# tommyprom.net
KiCad netlist of a schematic drawn in EAGLE
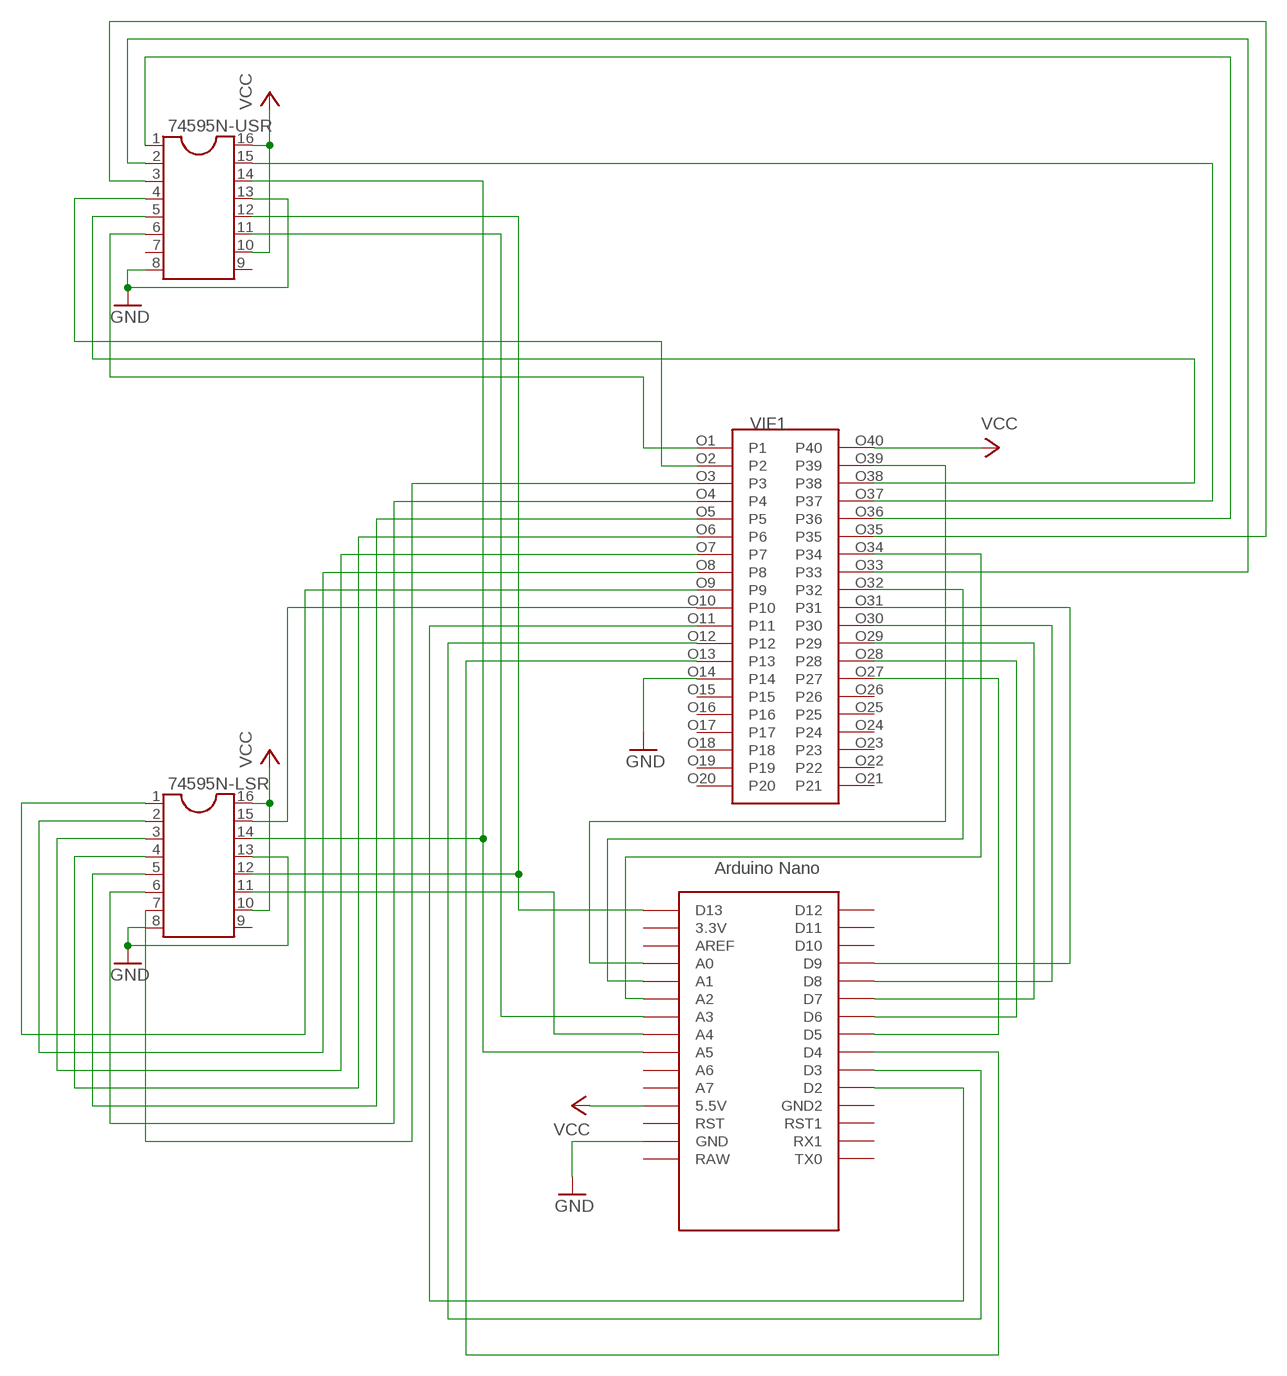
[diagram p0: schematic, sheet 1]

(export (version "E")
  (design (tool "Eeschema 10.0.6"))
  (components
    (comp (ref "74595N-LSR")
      (value "DIL16S")
      (footprint "eagle-import:SOCKET-16")
      (libsource (lib "eagle-import") (part "DIL16S"))
    )
    (comp (ref "74595N-USR")
      (value "DIL16S")
      (footprint "eagle-import:SOCKET-16")
      (libsource (lib "eagle-import") (part "DIL16S"))
    )
    (comp (ref "U$1")
      (value "NANO")
      (footprint "eagle-import:NANO")
      (libsource (lib "eagle-import") (part "NANO"))
    )
    (comp (ref "VIF1")
      (value "40-6554-10DIP")
      (footprint "eagle-import:40-6554-10")
      (libsource (lib "eagle-import") (part "40-6554-10DIP"))
    )
  )
  (nets
    (net (code "1") (name "GND") (class "Default")
      (node (ref "74595N-LSR") (pin "13") (pinfunction "13_13") (pintype "passive"))
      (node (ref "74595N-LSR") (pin "8") (pinfunction "8_8") (pintype "passive"))
      (node (ref "74595N-USR") (pin "13") (pinfunction "13_13") (pintype "passive"))
      (node (ref "74595N-USR") (pin "8") (pinfunction "8_8") (pintype "passive"))
      (node (ref "U$1") (pin "GND") (pinfunction "GND_GND") (pintype "bidirectional"))
      (node (ref "VIF1") (pin "O14") (pinfunction "P14_O14") (pintype "bidirectional"))
    )
    (net (code "2") (name "Net-(74595N-LSR-Pad11)") (class "Default")
      (node (ref "74595N-LSR") (pin "11") (pinfunction "11_11") (pintype "passive"))
      (node (ref "U$1") (pin "A4") (pinfunction "A4_A4") (pintype "bidirectional"))
    )
    (net (code "3") (name "Net-(74595N-LSR-Pad12)") (class "Default")
      (node (ref "74595N-LSR") (pin "12") (pinfunction "12_12") (pintype "passive"))
      (node (ref "74595N-USR") (pin "12") (pinfunction "12_12") (pintype "passive"))
      (node (ref "U$1") (pin "D13") (pinfunction "D13_D13") (pintype "bidirectional"))
    )
    (net (code "4") (name "Net-(74595N-LSR-Pad14)") (class "Default")
      (node (ref "74595N-LSR") (pin "14") (pinfunction "14_14") (pintype "passive"))
      (node (ref "74595N-USR") (pin "14") (pinfunction "14_14") (pintype "passive"))
      (node (ref "U$1") (pin "A5") (pinfunction "A5_A5") (pintype "bidirectional"))
    )
    (net (code "5") (name "Net-(74595N-USR-Pad11)") (class "Default")
      (node (ref "74595N-USR") (pin "11") (pinfunction "11_11") (pintype "passive"))
      (node (ref "U$1") (pin "A3") (pinfunction "A3_A3") (pintype "bidirectional"))
    )
    (net (code "6") (name "Net-(VIF1-P1)") (class "Default")
      (node (ref "74595N-USR") (pin "6") (pinfunction "6_6") (pintype "passive"))
      (node (ref "VIF1") (pin "O1") (pinfunction "P1_O1") (pintype "bidirectional"))
    )
    (net (code "7") (name "Net-(VIF1-P2)") (class "Default")
      (node (ref "74595N-USR") (pin "4") (pinfunction "4_4") (pintype "passive"))
      (node (ref "VIF1") (pin "O2") (pinfunction "P2_O2") (pintype "bidirectional"))
    )
    (net (code "8") (name "Net-(VIF1-P3)") (class "Default")
      (node (ref "74595N-LSR") (pin "7") (pinfunction "7_7") (pintype "passive"))
      (node (ref "VIF1") (pin "O3") (pinfunction "P3_O3") (pintype "bidirectional"))
    )
    (net (code "9") (name "Net-(VIF1-P4)") (class "Default")
      (node (ref "74595N-LSR") (pin "6") (pinfunction "6_6") (pintype "passive"))
      (node (ref "VIF1") (pin "O4") (pinfunction "P4_O4") (pintype "bidirectional"))
    )
    (net (code "10") (name "Net-(VIF1-P5)") (class "Default")
      (node (ref "74595N-LSR") (pin "5") (pinfunction "5_5") (pintype "passive"))
      (node (ref "VIF1") (pin "O5") (pinfunction "P5_O5") (pintype "bidirectional"))
    )
    (net (code "11") (name "Net-(VIF1-P6)") (class "Default")
      (node (ref "74595N-LSR") (pin "4") (pinfunction "4_4") (pintype "passive"))
      (node (ref "VIF1") (pin "O6") (pinfunction "P6_O6") (pintype "bidirectional"))
    )
    (net (code "12") (name "Net-(VIF1-P7)") (class "Default")
      (node (ref "74595N-LSR") (pin "3") (pinfunction "3_3") (pintype "passive"))
      (node (ref "VIF1") (pin "O7") (pinfunction "P7_O7") (pintype "bidirectional"))
    )
    (net (code "13") (name "Net-(VIF1-P8)") (class "Default")
      (node (ref "74595N-LSR") (pin "2") (pinfunction "2_2") (pintype "passive"))
      (node (ref "VIF1") (pin "O8") (pinfunction "P8_O8") (pintype "bidirectional"))
    )
    (net (code "14") (name "Net-(VIF1-P9)") (class "Default")
      (node (ref "74595N-LSR") (pin "1") (pinfunction "1_1") (pintype "passive"))
      (node (ref "VIF1") (pin "O9") (pinfunction "P9_O9") (pintype "bidirectional"))
    )
    (net (code "15") (name "Net-(VIF1-P10)") (class "Default")
      (node (ref "74595N-LSR") (pin "15") (pinfunction "15_15") (pintype "passive"))
      (node (ref "VIF1") (pin "O10") (pinfunction "P10_O10") (pintype "bidirectional"))
    )
    (net (code "16") (name "Net-(VIF1-P11)") (class "Default")
      (node (ref "U$1") (pin "D2") (pinfunction "D2_D2") (pintype "bidirectional"))
      (node (ref "VIF1") (pin "O11") (pinfunction "P11_O11") (pintype "bidirectional"))
    )
    (net (code "17") (name "Net-(VIF1-P12)") (class "Default")
      (node (ref "U$1") (pin "D3") (pinfunction "D3_D3") (pintype "bidirectional"))
      (node (ref "VIF1") (pin "O12") (pinfunction "P12_O12") (pintype "bidirectional"))
    )
    (net (code "18") (name "Net-(VIF1-P13)") (class "Default")
      (node (ref "U$1") (pin "D4") (pinfunction "D4_D4") (pintype "bidirectional"))
      (node (ref "VIF1") (pin "O13") (pinfunction "P13_O13") (pintype "bidirectional"))
    )
    (net (code "19") (name "Net-(VIF1-P27)") (class "Default")
      (node (ref "U$1") (pin "D5") (pinfunction "D5_D5") (pintype "bidirectional"))
      (node (ref "VIF1") (pin "O27") (pinfunction "P27_O27") (pintype "bidirectional"))
    )
    (net (code "20") (name "Net-(VIF1-P28)") (class "Default")
      (node (ref "U$1") (pin "D6") (pinfunction "D6_D6") (pintype "bidirectional"))
      (node (ref "VIF1") (pin "O28") (pinfunction "P28_O28") (pintype "bidirectional"))
    )
    (net (code "21") (name "Net-(VIF1-P29)") (class "Default")
      (node (ref "U$1") (pin "D7") (pinfunction "D7_D7") (pintype "bidirectional"))
      (node (ref "VIF1") (pin "O29") (pinfunction "P29_O29") (pintype "bidirectional"))
    )
    (net (code "22") (name "Net-(VIF1-P30)") (class "Default")
      (node (ref "U$1") (pin "D8") (pinfunction "D8_D8") (pintype "bidirectional"))
      (node (ref "VIF1") (pin "O30") (pinfunction "P30_O30") (pintype "bidirectional"))
    )
    (net (code "23") (name "Net-(VIF1-P31)") (class "Default")
      (node (ref "U$1") (pin "D9") (pinfunction "D9_D9") (pintype "bidirectional"))
      (node (ref "VIF1") (pin "O31") (pinfunction "P31_O31") (pintype "bidirectional"))
    )
    (net (code "24") (name "Net-(VIF1-P32)") (class "Default")
      (node (ref "U$1") (pin "A1") (pinfunction "A1_A1") (pintype "bidirectional"))
      (node (ref "VIF1") (pin "O32") (pinfunction "P32_O32") (pintype "bidirectional"))
    )
    (net (code "25") (name "Net-(VIF1-P33)") (class "Default")
      (node (ref "74595N-USR") (pin "2") (pinfunction "2_2") (pintype "passive"))
      (node (ref "VIF1") (pin "O33") (pinfunction "P33_O33") (pintype "bidirectional"))
    )
    (net (code "26") (name "Net-(VIF1-P34)") (class "Default")
      (node (ref "U$1") (pin "A2") (pinfunction "A2_A2") (pintype "bidirectional"))
      (node (ref "VIF1") (pin "O34") (pinfunction "P34_O34") (pintype "bidirectional"))
    )
    (net (code "27") (name "Net-(VIF1-P35)") (class "Default")
      (node (ref "74595N-USR") (pin "3") (pinfunction "3_3") (pintype "passive"))
      (node (ref "VIF1") (pin "O35") (pinfunction "P35_O35") (pintype "bidirectional"))
    )
    (net (code "28") (name "Net-(VIF1-P36)") (class "Default")
      (node (ref "74595N-USR") (pin "1") (pinfunction "1_1") (pintype "passive"))
      (node (ref "VIF1") (pin "O36") (pinfunction "P36_O36") (pintype "bidirectional"))
    )
    (net (code "29") (name "Net-(VIF1-P37)") (class "Default")
      (node (ref "74595N-USR") (pin "15") (pinfunction "15_15") (pintype "passive"))
      (node (ref "VIF1") (pin "O37") (pinfunction "P37_O37") (pintype "bidirectional"))
    )
    (net (code "30") (name "Net-(VIF1-P38)") (class "Default")
      (node (ref "74595N-USR") (pin "5") (pinfunction "5_5") (pintype "passive"))
      (node (ref "VIF1") (pin "O38") (pinfunction "P38_O38") (pintype "bidirectional"))
    )
    (net (code "31") (name "Net-(VIF1-P39)") (class "Default")
      (node (ref "U$1") (pin "A0") (pinfunction "A0_A0") (pintype "bidirectional"))
      (node (ref "VIF1") (pin "O39") (pinfunction "P39_O39") (pintype "bidirectional"))
    )
    (net (code "32") (name "VCC") (class "Default")
      (node (ref "74595N-LSR") (pin "10") (pinfunction "10_10") (pintype "passive"))
      (node (ref "74595N-LSR") (pin "16") (pinfunction "16_16") (pintype "passive"))
      (node (ref "74595N-USR") (pin "10") (pinfunction "10_10") (pintype "passive"))
      (node (ref "74595N-USR") (pin "16") (pinfunction "16_16") (pintype "passive"))
      (node (ref "U$1") (pin "5V") (pinfunction "5.5V_5V") (pintype "bidirectional"))
      (node (ref "VIF1") (pin "O40") (pinfunction "P40_O40") (pintype "bidirectional"))
    )
    (net (code "33") (name "unconnected-(74595N-LSR-Pad9)") (class "Default")
      (node (ref "74595N-LSR") (pin "9") (pinfunction "9_9") (pintype "passive"))
    )
    (net (code "34") (name "unconnected-(74595N-USR-Pad7)") (class "Default")
      (node (ref "74595N-USR") (pin "7") (pinfunction "7_7") (pintype "passive"))
    )
    (net (code "35") (name "unconnected-(74595N-USR-Pad9)") (class "Default")
      (node (ref "74595N-USR") (pin "9") (pinfunction "9_9") (pintype "passive"))
    )
    (net (code "36") (name "unconnected-(U$1-GND2-PadGND1)") (class "Default")
      (node (ref "U$1") (pin "GND1") (pinfunction "GND2_GND1") (pintype "bidirectional"))
    )
    (net (code "37") (name "unconnected-(U$1-Pad3.3V)") (class "Default")
      (node (ref "U$1") (pin "3.3V") (pinfunction "3.3V_3.3V") (pintype "bidirectional"))
    )
    (net (code "38") (name "unconnected-(U$1-PadA6)") (class "Default")
      (node (ref "U$1") (pin "A6") (pinfunction "A6_A6") (pintype "bidirectional"))
    )
    (net (code "39") (name "unconnected-(U$1-PadA7)") (class "Default")
      (node (ref "U$1") (pin "A7") (pinfunction "A7_A7") (pintype "bidirectional"))
    )
    (net (code "40") (name "unconnected-(U$1-PadAREF)") (class "Default")
      (node (ref "U$1") (pin "AREF") (pinfunction "AREF_AREF") (pintype "bidirectional"))
    )
    (net (code "41") (name "unconnected-(U$1-PadD10)") (class "Default")
      (node (ref "U$1") (pin "D10") (pinfunction "D10_D10") (pintype "bidirectional"))
    )
    (net (code "42") (name "unconnected-(U$1-PadD11)") (class "Default")
      (node (ref "U$1") (pin "D11") (pinfunction "D11_D11") (pintype "bidirectional"))
    )
    (net (code "43") (name "unconnected-(U$1-PadD12)") (class "Default")
      (node (ref "U$1") (pin "D12") (pinfunction "D12_D12") (pintype "bidirectional"))
    )
    (net (code "44") (name "unconnected-(U$1-PadICSP1)") (class "Default")
      (node (ref "U$1") (pin "ICSP1") (pinfunction "ICSP1_ICSP1") (pintype "bidirectional"))
    )
    (net (code "45") (name "unconnected-(U$1-PadICSP2)") (class "Default")
      (node (ref "U$1") (pin "ICSP2") (pinfunction "ICSP2_ICSP2") (pintype "bidirectional"))
    )
    (net (code "46") (name "unconnected-(U$1-PadICSP3)") (class "Default")
      (node (ref "U$1") (pin "ICSP3") (pinfunction "ICSP3_ICSP3") (pintype "bidirectional"))
    )
    (net (code "47") (name "unconnected-(U$1-PadICSP4)") (class "Default")
      (node (ref "U$1") (pin "ICSP4") (pinfunction "ICSP4_ICSP4") (pintype "bidirectional"))
    )
    (net (code "48") (name "unconnected-(U$1-PadICSP5)") (class "Default")
      (node (ref "U$1") (pin "ICSP5") (pinfunction "ICSP5_ICSP5") (pintype "bidirectional"))
    )
    (net (code "49") (name "unconnected-(U$1-PadICSP6)") (class "Default")
      (node (ref "U$1") (pin "ICSP6") (pinfunction "ICSP6_ICSP6") (pintype "bidirectional"))
    )
    (net (code "50") (name "unconnected-(U$1-PadRAW)") (class "Default")
      (node (ref "U$1") (pin "RAW") (pinfunction "RAW_RAW") (pintype "bidirectional"))
    )
    (net (code "51") (name "unconnected-(U$1-PadRST)") (class "Default")
      (node (ref "U$1") (pin "RST") (pinfunction "RST_RST") (pintype "bidirectional"))
    )
    (net (code "52") (name "unconnected-(U$1-PadRST1)") (class "Default")
      (node (ref "U$1") (pin "RST1") (pinfunction "RST1_RST1") (pintype "bidirectional"))
    )
    (net (code "53") (name "unconnected-(U$1-PadRX1)") (class "Default")
      (node (ref "U$1") (pin "RX1") (pinfunction "RX1_RX1") (pintype "bidirectional"))
    )
    (net (code "54") (name "unconnected-(U$1-PadTX0)") (class "Default")
      (node (ref "U$1") (pin "TX0") (pinfunction "TX0_TX0") (pintype "bidirectional"))
    )
    (net (code "55") (name "unconnected-(VIF1-P15-PadO15)") (class "Default")
      (node (ref "VIF1") (pin "O15") (pinfunction "P15_O15") (pintype "bidirectional"))
    )
    (net (code "56") (name "unconnected-(VIF1-P16-PadO16)") (class "Default")
      (node (ref "VIF1") (pin "O16") (pinfunction "P16_O16") (pintype "bidirectional"))
    )
    (net (code "57") (name "unconnected-(VIF1-P17-PadO17)") (class "Default")
      (node (ref "VIF1") (pin "O17") (pinfunction "P17_O17") (pintype "bidirectional"))
    )
    (net (code "58") (name "unconnected-(VIF1-P18-PadO18)") (class "Default")
      (node (ref "VIF1") (pin "O18") (pinfunction "P18_O18") (pintype "bidirectional"))
    )
    (net (code "59") (name "unconnected-(VIF1-P19-PadO19)") (class "Default")
      (node (ref "VIF1") (pin "O19") (pinfunction "P19_O19") (pintype "bidirectional"))
    )
    (net (code "60") (name "unconnected-(VIF1-P20-PadO20)") (class "Default")
      (node (ref "VIF1") (pin "O20") (pinfunction "P20_O20") (pintype "bidirectional"))
    )
    (net (code "61") (name "unconnected-(VIF1-P21-PadO21)") (class "Default")
      (node (ref "VIF1") (pin "O21") (pinfunction "P21_O21") (pintype "bidirectional"))
    )
    (net (code "62") (name "unconnected-(VIF1-P22-PadO22)") (class "Default")
      (node (ref "VIF1") (pin "O22") (pinfunction "P22_O22") (pintype "bidirectional"))
    )
    (net (code "63") (name "unconnected-(VIF1-P23-PadO23)") (class "Default")
      (node (ref "VIF1") (pin "O23") (pinfunction "P23_O23") (pintype "bidirectional"))
    )
    (net (code "64") (name "unconnected-(VIF1-P24-PadO24)") (class "Default")
      (node (ref "VIF1") (pin "O24") (pinfunction "P24_O24") (pintype "bidirectional"))
    )
    (net (code "65") (name "unconnected-(VIF1-P25-PadO25)") (class "Default")
      (node (ref "VIF1") (pin "O25") (pinfunction "P25_O25") (pintype "bidirectional"))
    )
    (net (code "66") (name "unconnected-(VIF1-P26-PadO26)") (class "Default")
      (node (ref "VIF1") (pin "O26") (pinfunction "P26_O26") (pintype "bidirectional"))
    )
  )
)
